# 10-Programmer.net
KiCad netlist of a schematic drawn in Altium Designer
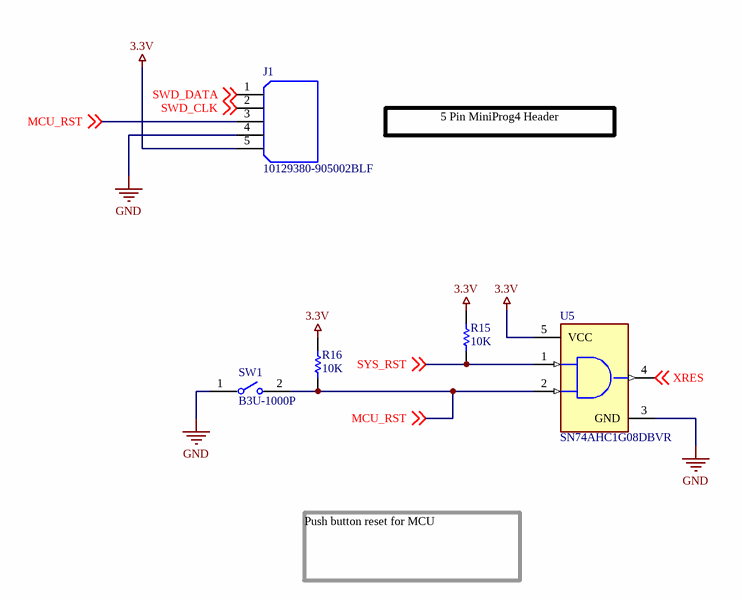
[diagram p0: 10-Programmer.SchDoc]

(export (version "E")
  (design (tool "Eeschema 10.0.6"))
  (components
    (comp (ref "J1")
      (value "10129380-905002BLF")
      (footprint "AMPHENOL_10129380-905002BLF")
      (description "Conn Unshrouded Header HDR 5 POS 2.54mm Solder ST SMD Poly Bag")
      (fields (field (name "MF") "AMPHENOL ICC / FCI"))
      (libsource (lib "ece353-2022") (part "10129380-905002BLF"))
    )
    (comp (ref "R15")
      (value "RC1206FR-0710KL")
      (footprint "RESC3116X65X40ML10T20")
      (description "Chip Resistor, 10 KOhm, +/- 1%, 0.25 W, -55 to 155 degC, 1206 (3216 Metric), RoHS, Tape and Reel")
      (fields
        (field (name "TOLERANCE") "1%")
        (field (name "RESISTANCE") "10K")
        (field (name "MANUFACTURER") "Yageo")
      )
      (libsource (lib "Altium Content Vault") (part "RES-2"))
    )
    (comp (ref "R16")
      (value "RC1206FR-0710KL")
      (footprint "RESC3116X65X40ML10T20")
      (description "Chip Resistor, 10 KOhm, +/- 1%, 0.25 W, -55 to 155 degC, 1206 (3216 Metric), RoHS, Tape and Reel")
      (fields
        (field (name "TOLERANCE") "1%")
        (field (name "RESISTANCE") "10K")
        (field (name "MANUFACTURER") "Yageo")
      )
      (libsource (lib "Altium Content Vault") (part "RES-2"))
    )
    (comp (ref "SW1")
      (value "B3U-1000P")
      (footprint "FP-B3U-1000P-MFG")
      (description "SWITCH TACTILE SPST-NO 0.05A 12V")
      (fields (field (name "MANUFACTURER") "Omron"))
      (libsource (lib "Altium Content Vault") (part "ae622034201233ca1abcedc05908f33"))
    )
    (comp (ref "U5")
      (value "SN74AHC1G08DBVR")
      (footprint "FP-DBV0005A-MFG")
      (description "IC GATE AND 1CH 2-INP SOT23-5")
      (fields
        (field (name "MANUFACTURER") "Texas Instruments")
        (field (name "OCTOPART") "https://octopart.com/sn74ahc1g08dbvr-texas+instruments-464404")
      )
      (libsource (lib "Altium Content Vault") (part "7d5472fad8fac2169e6b8dda8b756c7"))
    )
  )
  (nets
    (net (code "1") (name "3.3V") (class "Default")
      (node (ref "J1") (pin "5") (pinfunction "5_5") (pintype "passive"))
      (node (ref "R15") (pin "2") (pinfunction "2_2") (pintype "passive"))
      (node (ref "R16") (pin "2") (pinfunction "2_2") (pintype "passive"))
      (node (ref "U5") (pin "5") (pinfunction "VCC_5") (pintype "power_in"))
    )
    (net (code "2") (name "GND") (class "Default")
      (node (ref "J1") (pin "4") (pinfunction "4_4") (pintype "passive"))
      (node (ref "SW1") (pin "1") (pinfunction "1_1") (pintype "passive"))
      (node (ref "U5") (pin "3") (pinfunction "GND_3") (pintype "power_in"))
    )
    (net (code "3") (name "MCU_RST") (class "Default")
      (node (ref "J1") (pin "3") (pinfunction "3_3") (pintype "passive"))
      (node (ref "R16") (pin "1") (pinfunction "1_1") (pintype "passive"))
      (node (ref "SW1") (pin "2") (pinfunction "2_2") (pintype "passive"))
      (node (ref "U5") (pin "2") (pinfunction "B_2") (pintype "input"))
    )
    (net (code "4") (name "SWD_CLK") (class "Default")
      (node (ref "J1") (pin "2") (pinfunction "2_2") (pintype "passive"))
    )
    (net (code "5") (name "SWD_DATA") (class "Default")
      (node (ref "J1") (pin "1") (pinfunction "1_1") (pintype "passive"))
    )
    (net (code "6") (name "SYS_RST") (class "Default")
      (node (ref "R15") (pin "1") (pinfunction "1_1") (pintype "passive"))
      (node (ref "U5") (pin "1") (pinfunction "A_1") (pintype "input"))
    )
    (net (code "7") (name "XRES") (class "Default")
      (node (ref "U5") (pin "4") (pinfunction "Y_4") (pintype "output"))
    )
  )
)
